# PGTNX07_gate_out.net
KiCad netlist of a schematic drawn in EAGLE
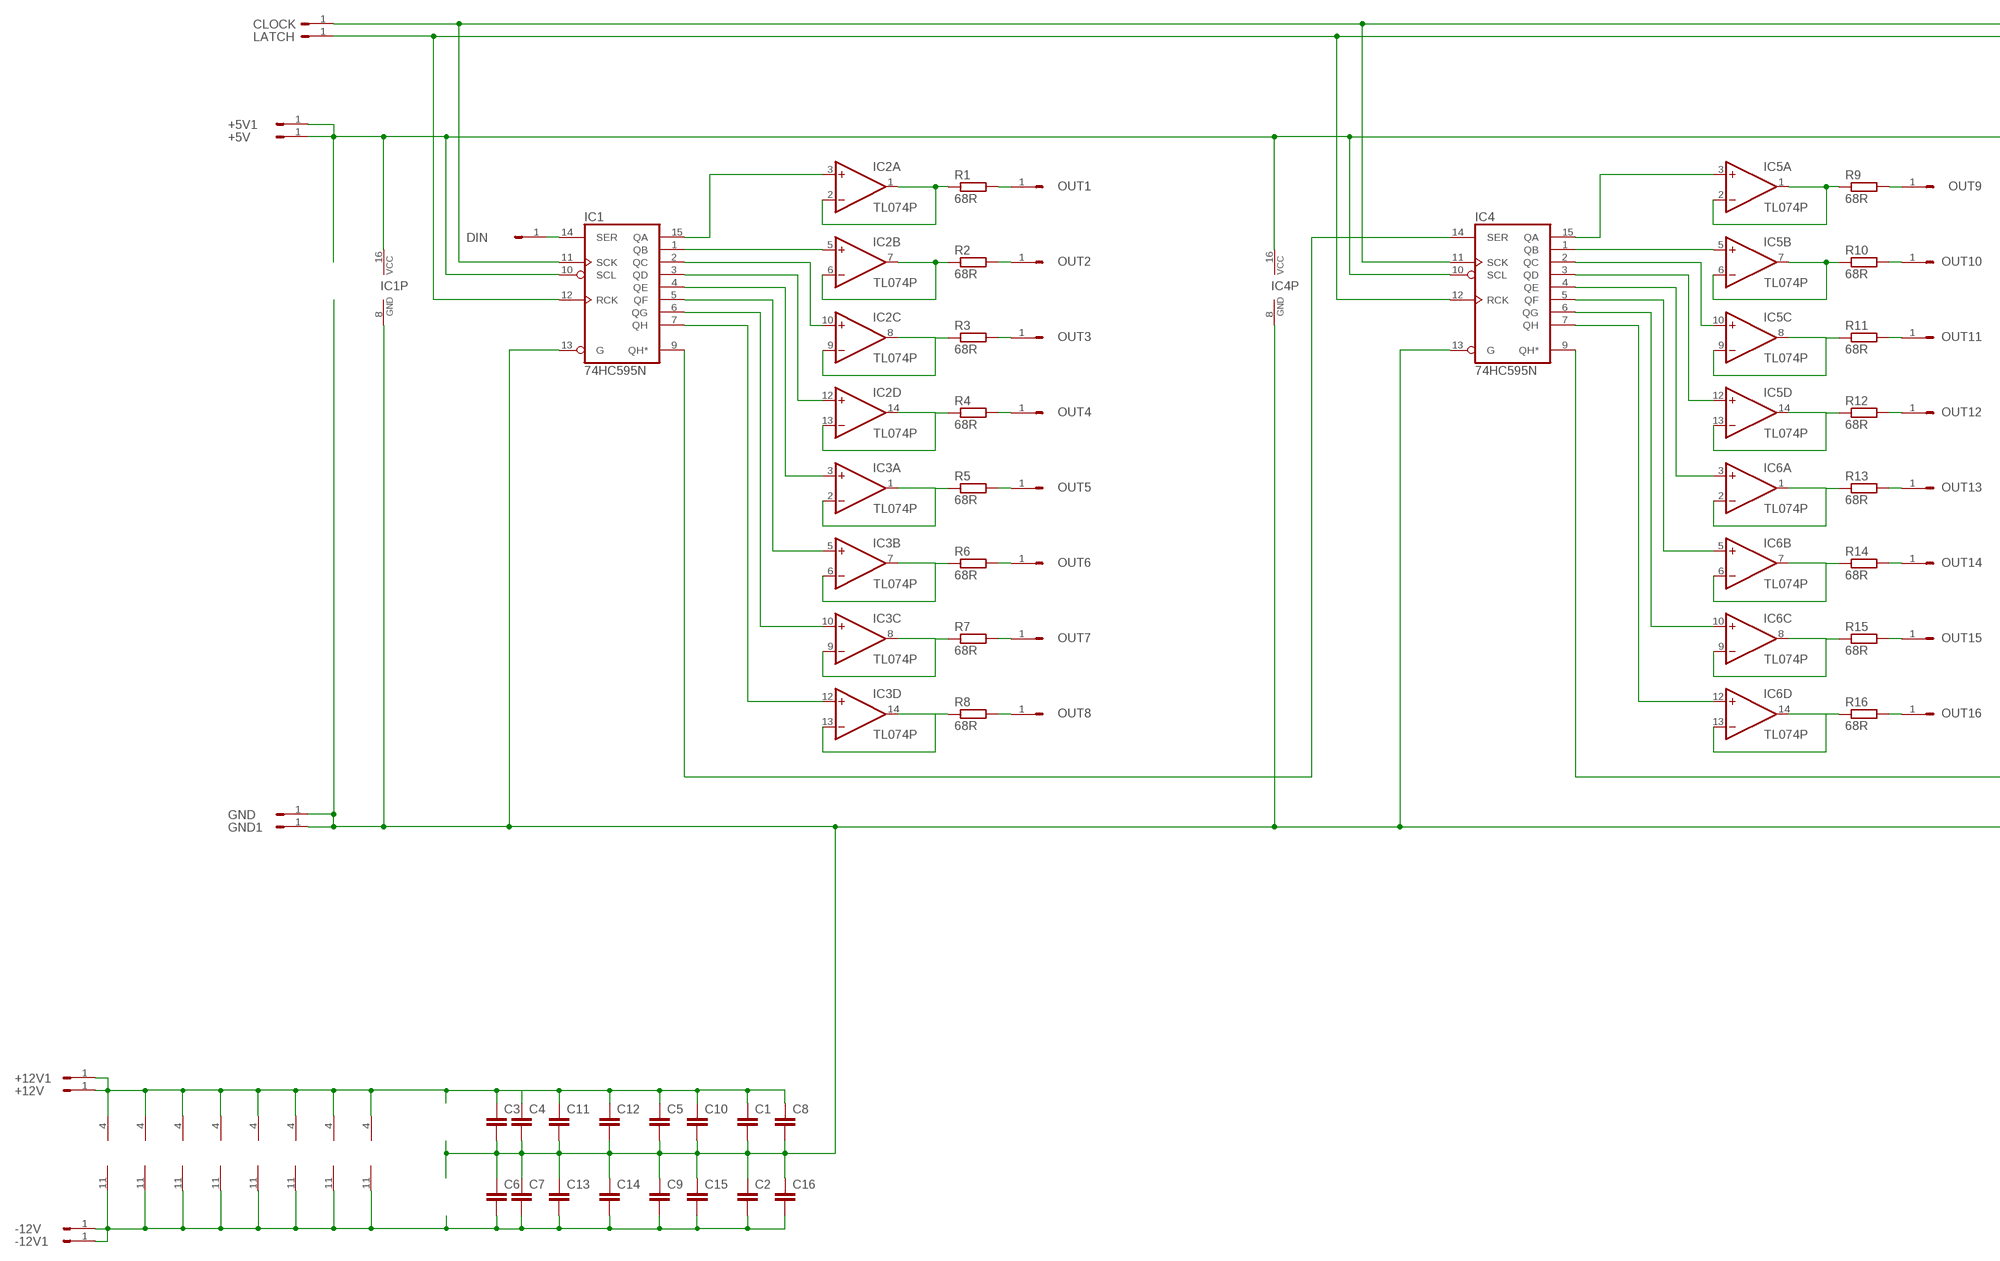
[diagram p0: schematic, sheet 1, part 1 of 2]
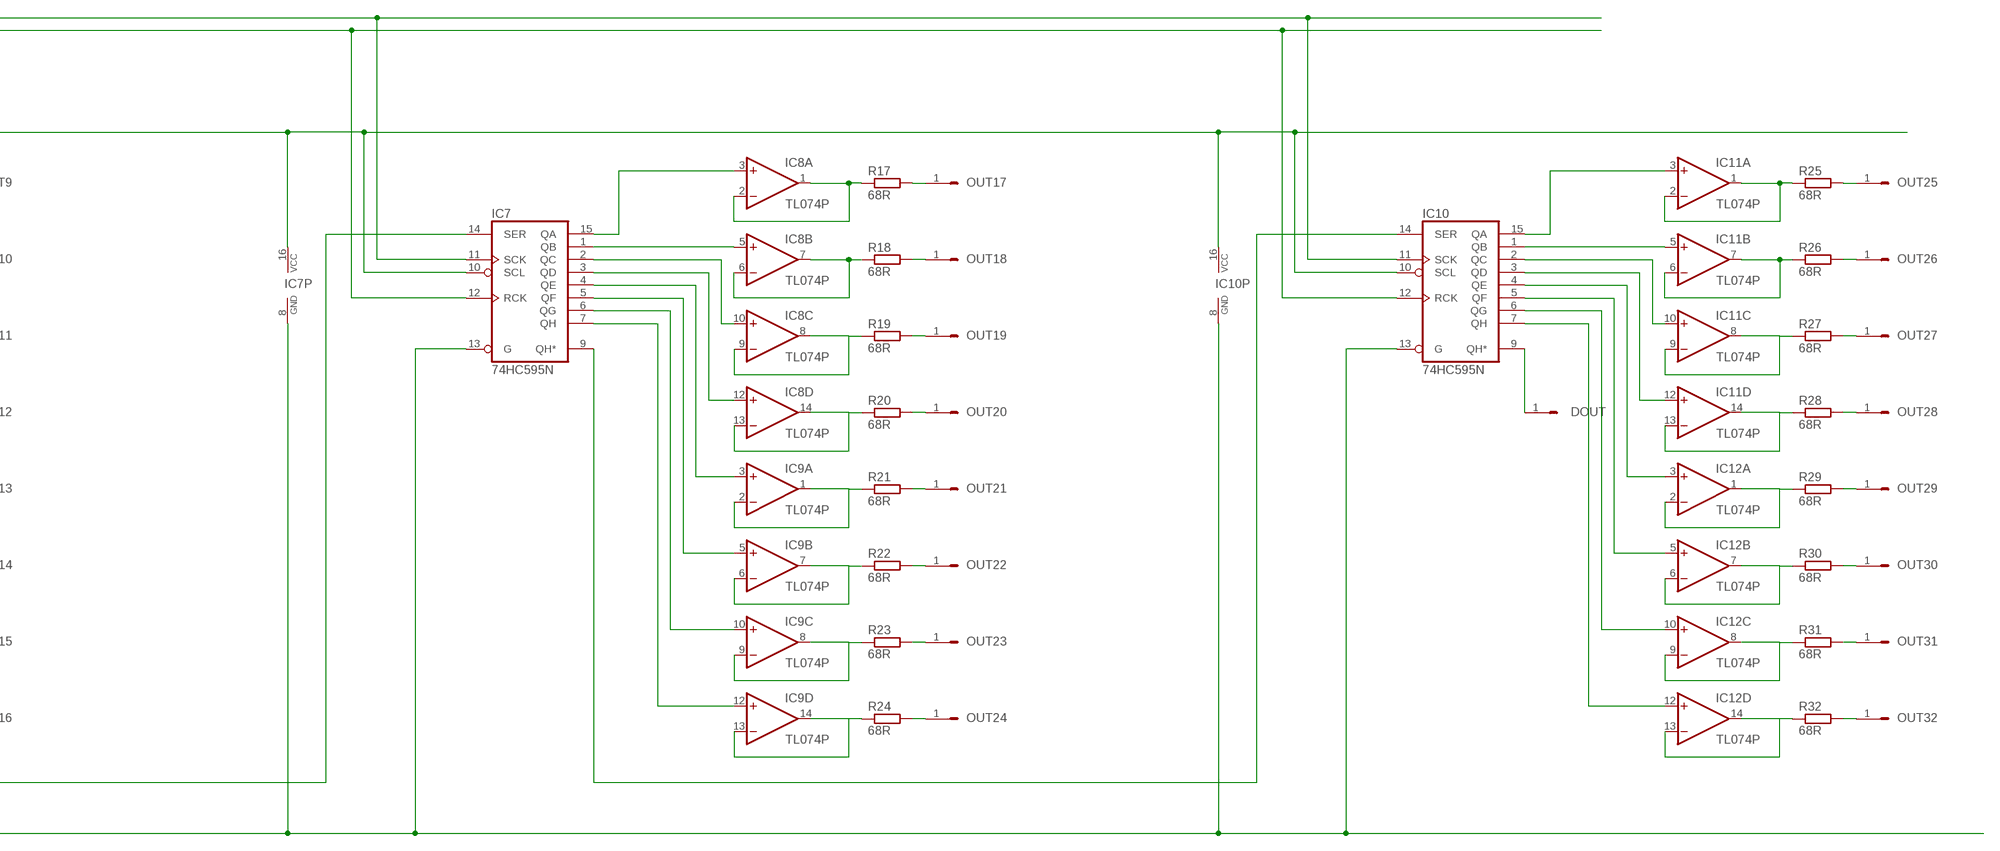
[diagram p1: schematic, sheet 1, part 2 of 2]

(export (version "E")
  (design (tool "Eeschema 10.0.6"))
  (components
    (comp (ref "+5V")
      (value "HEADER/MALE/01")
      (footprint "eagle-import:HEADER_MALE_01")
      (libsource (lib "eagle-import") (part "HEADER/MALE/01"))
    )
    (comp (ref "+5V1")
      (value "HEADER/MALE/01")
      (footprint "eagle-import:HEADER_MALE_01")
      (libsource (lib "eagle-import") (part "HEADER/MALE/01"))
    )
    (comp (ref "+12V")
      (value "HEADER/MALE/01")
      (footprint "eagle-import:HEADER_MALE_01")
      (libsource (lib "eagle-import") (part "HEADER/MALE/01"))
    )
    (comp (ref "+12V1")
      (value "HEADER/MALE/01")
      (footprint "eagle-import:HEADER_MALE_01")
      (libsource (lib "eagle-import") (part "HEADER/MALE/01"))
    )
    (comp (ref "-12V")
      (value "HEADER/MALE/01")
      (footprint "eagle-import:HEADER_MALE_01")
      (libsource (lib "eagle-import") (part "HEADER/MALE/01"))
    )
    (comp (ref "-12V1")
      (value "HEADER/MALE/01")
      (footprint "eagle-import:HEADER_MALE_01")
      (libsource (lib "eagle-import") (part "HEADER/MALE/01"))
    )
    (comp (ref "C1")
      (value "CAPACITORCERAMICDISC/5")
      (footprint "eagle-import:CERAMICDISC_5")
      (libsource (lib "eagle-import") (part "CAPACITORCERAMICDISC/5"))
    )
    (comp (ref "C2")
      (value "CAPACITORCERAMICDISC/5")
      (footprint "eagle-import:CERAMICDISC_5")
      (libsource (lib "eagle-import") (part "CAPACITORCERAMICDISC/5"))
    )
    (comp (ref "C3")
      (value "CAPACITORCERAMICDISC/5")
      (footprint "eagle-import:CERAMICDISC_5")
      (libsource (lib "eagle-import") (part "CAPACITORCERAMICDISC/5"))
    )
    (comp (ref "C4")
      (value "CAPACITORCERAMICDISC/5")
      (footprint "eagle-import:CERAMICDISC_5")
      (libsource (lib "eagle-import") (part "CAPACITORCERAMICDISC/5"))
    )
    (comp (ref "C5")
      (value "CAPACITORCERAMICDISC/5")
      (footprint "eagle-import:CERAMICDISC_5")
      (libsource (lib "eagle-import") (part "CAPACITORCERAMICDISC/5"))
    )
    (comp (ref "C6")
      (value "CAPACITORCERAMICDISC/5")
      (footprint "eagle-import:CERAMICDISC_5")
      (libsource (lib "eagle-import") (part "CAPACITORCERAMICDISC/5"))
    )
    (comp (ref "C7")
      (value "CAPACITORCERAMICDISC/5")
      (footprint "eagle-import:CERAMICDISC_5")
      (libsource (lib "eagle-import") (part "CAPACITORCERAMICDISC/5"))
    )
    (comp (ref "C8")
      (value "CAPACITORCERAMICDISC/5")
      (footprint "eagle-import:CERAMICDISC_5")
      (libsource (lib "eagle-import") (part "CAPACITORCERAMICDISC/5"))
    )
    (comp (ref "C9")
      (value "CAPACITORCERAMICDISC/5")
      (footprint "eagle-import:CERAMICDISC_5")
      (libsource (lib "eagle-import") (part "CAPACITORCERAMICDISC/5"))
    )
    (comp (ref "C10")
      (value "CAPACITORCERAMICDISC/5")
      (footprint "eagle-import:CERAMICDISC_5")
      (libsource (lib "eagle-import") (part "CAPACITORCERAMICDISC/5"))
    )
    (comp (ref "C11")
      (value "CAPACITORCERAMICDISC/5")
      (footprint "eagle-import:CERAMICDISC_5")
      (libsource (lib "eagle-import") (part "CAPACITORCERAMICDISC/5"))
    )
    (comp (ref "C12")
      (value "CAPACITORCERAMICDISC/5")
      (footprint "eagle-import:CERAMICDISC_5")
      (libsource (lib "eagle-import") (part "CAPACITORCERAMICDISC/5"))
    )
    (comp (ref "C13")
      (value "CAPACITORCERAMICDISC/5")
      (footprint "eagle-import:CERAMICDISC_5")
      (libsource (lib "eagle-import") (part "CAPACITORCERAMICDISC/5"))
    )
    (comp (ref "C14")
      (value "CAPACITORCERAMICDISC/5")
      (footprint "eagle-import:CERAMICDISC_5")
      (libsource (lib "eagle-import") (part "CAPACITORCERAMICDISC/5"))
    )
    (comp (ref "C15")
      (value "CAPACITORCERAMICDISC/5")
      (footprint "eagle-import:CERAMICDISC_5")
      (libsource (lib "eagle-import") (part "CAPACITORCERAMICDISC/5"))
    )
    (comp (ref "C16")
      (value "CAPACITORCERAMICDISC/5")
      (footprint "eagle-import:CERAMICDISC_5")
      (libsource (lib "eagle-import") (part "CAPACITORCERAMICDISC/5"))
    )
    (comp (ref "CLOCK")
      (value "HEADER/MALE/01")
      (footprint "eagle-import:HEADER_MALE_01")
      (libsource (lib "eagle-import") (part "HEADER/MALE/01"))
    )
    (comp (ref "DIN")
      (value "HEADER/MALE/01")
      (footprint "eagle-import:HEADER_MALE_01")
      (libsource (lib "eagle-import") (part "HEADER/MALE/01"))
    )
    (comp (ref "DOUT")
      (value "HEADER/MALE/01")
      (footprint "eagle-import:HEADER_MALE_01")
      (libsource (lib "eagle-import") (part "HEADER/MALE/01"))
    )
    (comp (ref "GND")
      (value "HEADER/MALE/01")
      (footprint "eagle-import:HEADER_MALE_01")
      (libsource (lib "eagle-import") (part "HEADER/MALE/01"))
    )
    (comp (ref "GND1")
      (value "HEADER/MALE/01")
      (footprint "eagle-import:HEADER_MALE_01")
      (libsource (lib "eagle-import") (part "HEADER/MALE/01"))
    )
    (comp (ref "IC1")
      (value "74HC595N")
      (footprint "eagle-import:DIL16")
      (libsource (lib "eagle-import") (part "74595NHC"))
    )
    (comp (ref "IC2")
      (value "TL074P")
      (footprint "eagle-import:DIL14")
      (libsource (lib "eagle-import") (part "TL074P"))
    )
    (comp (ref "IC3")
      (value "TL074P")
      (footprint "eagle-import:DIL14")
      (libsource (lib "eagle-import") (part "TL074P"))
    )
    (comp (ref "IC4")
      (value "74HC595N")
      (footprint "eagle-import:DIL16")
      (libsource (lib "eagle-import") (part "74595NHC"))
    )
    (comp (ref "IC5")
      (value "TL074P")
      (footprint "eagle-import:DIL14")
      (libsource (lib "eagle-import") (part "TL074P"))
    )
    (comp (ref "IC6")
      (value "TL074P")
      (footprint "eagle-import:DIL14")
      (libsource (lib "eagle-import") (part "TL074P"))
    )
    (comp (ref "IC7")
      (value "74HC595N")
      (footprint "eagle-import:DIL16")
      (libsource (lib "eagle-import") (part "74595NHC"))
    )
    (comp (ref "IC8")
      (value "TL074P")
      (footprint "eagle-import:DIL14")
      (libsource (lib "eagle-import") (part "TL074P"))
    )
    (comp (ref "IC9")
      (value "TL074P")
      (footprint "eagle-import:DIL14")
      (libsource (lib "eagle-import") (part "TL074P"))
    )
    (comp (ref "IC10")
      (value "74HC595N")
      (footprint "eagle-import:DIL16")
      (libsource (lib "eagle-import") (part "74595NHC"))
    )
    (comp (ref "IC11")
      (value "TL074P")
      (footprint "eagle-import:DIL14")
      (libsource (lib "eagle-import") (part "TL074P"))
    )
    (comp (ref "IC12")
      (value "TL074P")
      (footprint "eagle-import:DIL14")
      (libsource (lib "eagle-import") (part "TL074P"))
    )
    (comp (ref "LATCH")
      (value "HEADER/MALE/01")
      (footprint "eagle-import:HEADER_MALE_01")
      (libsource (lib "eagle-import") (part "HEADER/MALE/01"))
    )
    (comp (ref "OUT1")
      (value "HEADER/MALE/01")
      (footprint "eagle-import:HEADER_MALE_01")
      (libsource (lib "eagle-import") (part "HEADER/MALE/01"))
    )
    (comp (ref "OUT2")
      (value "HEADER/MALE/01")
      (footprint "eagle-import:HEADER_MALE_01")
      (libsource (lib "eagle-import") (part "HEADER/MALE/01"))
    )
    (comp (ref "OUT3")
      (value "HEADER/MALE/01")
      (footprint "eagle-import:HEADER_MALE_01")
      (libsource (lib "eagle-import") (part "HEADER/MALE/01"))
    )
    (comp (ref "OUT4")
      (value "HEADER/MALE/01")
      (footprint "eagle-import:HEADER_MALE_01")
      (libsource (lib "eagle-import") (part "HEADER/MALE/01"))
    )
    (comp (ref "OUT5")
      (value "HEADER/MALE/01")
      (footprint "eagle-import:HEADER_MALE_01")
      (libsource (lib "eagle-import") (part "HEADER/MALE/01"))
    )
    (comp (ref "OUT6")
      (value "HEADER/MALE/01")
      (footprint "eagle-import:HEADER_MALE_01")
      (libsource (lib "eagle-import") (part "HEADER/MALE/01"))
    )
    (comp (ref "OUT7")
      (value "HEADER/MALE/01")
      (footprint "eagle-import:HEADER_MALE_01")
      (libsource (lib "eagle-import") (part "HEADER/MALE/01"))
    )
    (comp (ref "OUT8")
      (value "HEADER/MALE/01")
      (footprint "eagle-import:HEADER_MALE_01")
      (libsource (lib "eagle-import") (part "HEADER/MALE/01"))
    )
    (comp (ref "OUT9")
      (value "HEADER/MALE/01")
      (footprint "eagle-import:HEADER_MALE_01")
      (libsource (lib "eagle-import") (part "HEADER/MALE/01"))
    )
    (comp (ref "OUT10")
      (value "HEADER/MALE/01")
      (footprint "eagle-import:HEADER_MALE_01")
      (libsource (lib "eagle-import") (part "HEADER/MALE/01"))
    )
    (comp (ref "OUT11")
      (value "HEADER/MALE/01")
      (footprint "eagle-import:HEADER_MALE_01")
      (libsource (lib "eagle-import") (part "HEADER/MALE/01"))
    )
    (comp (ref "OUT12")
      (value "HEADER/MALE/01")
      (footprint "eagle-import:HEADER_MALE_01")
      (libsource (lib "eagle-import") (part "HEADER/MALE/01"))
    )
    (comp (ref "OUT13")
      (value "HEADER/MALE/01")
      (footprint "eagle-import:HEADER_MALE_01")
      (libsource (lib "eagle-import") (part "HEADER/MALE/01"))
    )
    (comp (ref "OUT14")
      (value "HEADER/MALE/01")
      (footprint "eagle-import:HEADER_MALE_01")
      (libsource (lib "eagle-import") (part "HEADER/MALE/01"))
    )
    (comp (ref "OUT15")
      (value "HEADER/MALE/01")
      (footprint "eagle-import:HEADER_MALE_01")
      (libsource (lib "eagle-import") (part "HEADER/MALE/01"))
    )
    (comp (ref "OUT16")
      (value "HEADER/MALE/01")
      (footprint "eagle-import:HEADER_MALE_01")
      (libsource (lib "eagle-import") (part "HEADER/MALE/01"))
    )
    (comp (ref "OUT17")
      (value "HEADER/MALE/01")
      (footprint "eagle-import:HEADER_MALE_01")
      (libsource (lib "eagle-import") (part "HEADER/MALE/01"))
    )
    (comp (ref "OUT18")
      (value "HEADER/MALE/01")
      (footprint "eagle-import:HEADER_MALE_01")
      (libsource (lib "eagle-import") (part "HEADER/MALE/01"))
    )
    (comp (ref "OUT19")
      (value "HEADER/MALE/01")
      (footprint "eagle-import:HEADER_MALE_01")
      (libsource (lib "eagle-import") (part "HEADER/MALE/01"))
    )
    (comp (ref "OUT20")
      (value "HEADER/MALE/01")
      (footprint "eagle-import:HEADER_MALE_01")
      (libsource (lib "eagle-import") (part "HEADER/MALE/01"))
    )
    (comp (ref "OUT21")
      (value "HEADER/MALE/01")
      (footprint "eagle-import:HEADER_MALE_01")
      (libsource (lib "eagle-import") (part "HEADER/MALE/01"))
    )
    (comp (ref "OUT22")
      (value "HEADER/MALE/01")
      (footprint "eagle-import:HEADER_MALE_01")
      (libsource (lib "eagle-import") (part "HEADER/MALE/01"))
    )
    (comp (ref "OUT23")
      (value "HEADER/MALE/01")
      (footprint "eagle-import:HEADER_MALE_01")
      (libsource (lib "eagle-import") (part "HEADER/MALE/01"))
    )
    (comp (ref "OUT24")
      (value "HEADER/MALE/01")
      (footprint "eagle-import:HEADER_MALE_01")
      (libsource (lib "eagle-import") (part "HEADER/MALE/01"))
    )
    (comp (ref "OUT25")
      (value "HEADER/MALE/01")
      (footprint "eagle-import:HEADER_MALE_01")
      (libsource (lib "eagle-import") (part "HEADER/MALE/01"))
    )
    (comp (ref "OUT26")
      (value "HEADER/MALE/01")
      (footprint "eagle-import:HEADER_MALE_01")
      (libsource (lib "eagle-import") (part "HEADER/MALE/01"))
    )
    (comp (ref "OUT27")
      (value "HEADER/MALE/01")
      (footprint "eagle-import:HEADER_MALE_01")
      (libsource (lib "eagle-import") (part "HEADER/MALE/01"))
    )
    (comp (ref "OUT28")
      (value "HEADER/MALE/01")
      (footprint "eagle-import:HEADER_MALE_01")
      (libsource (lib "eagle-import") (part "HEADER/MALE/01"))
    )
    (comp (ref "OUT29")
      (value "HEADER/MALE/01")
      (footprint "eagle-import:HEADER_MALE_01")
      (libsource (lib "eagle-import") (part "HEADER/MALE/01"))
    )
    (comp (ref "OUT30")
      (value "HEADER/MALE/01")
      (footprint "eagle-import:HEADER_MALE_01")
      (libsource (lib "eagle-import") (part "HEADER/MALE/01"))
    )
    (comp (ref "OUT31")
      (value "HEADER/MALE/01")
      (footprint "eagle-import:HEADER_MALE_01")
      (libsource (lib "eagle-import") (part "HEADER/MALE/01"))
    )
    (comp (ref "OUT32")
      (value "HEADER/MALE/01")
      (footprint "eagle-import:HEADER_MALE_01")
      (libsource (lib "eagle-import") (part "HEADER/MALE/01"))
    )
    (comp (ref "R1")
      (value "68R")
      (footprint "eagle-import:RESISTOR_7.5")
      (libsource (lib "eagle-import") (part "RESISTORRESISTOR/UPRIGHT/7.5"))
    )
    (comp (ref "R2")
      (value "68R")
      (footprint "eagle-import:RESISTOR_7.5")
      (libsource (lib "eagle-import") (part "RESISTORRESISTOR/UPRIGHT/7.5"))
    )
    (comp (ref "R3")
      (value "68R")
      (footprint "eagle-import:RESISTOR_7.5")
      (libsource (lib "eagle-import") (part "RESISTORRESISTOR/UPRIGHT/7.5"))
    )
    (comp (ref "R4")
      (value "68R")
      (footprint "eagle-import:RESISTOR_7.5")
      (libsource (lib "eagle-import") (part "RESISTORRESISTOR/UPRIGHT/7.5"))
    )
    (comp (ref "R5")
      (value "68R")
      (footprint "eagle-import:RESISTOR_7.5")
      (libsource (lib "eagle-import") (part "RESISTORRESISTOR/UPRIGHT/7.5"))
    )
    (comp (ref "R6")
      (value "68R")
      (footprint "eagle-import:RESISTOR_7.5")
      (libsource (lib "eagle-import") (part "RESISTORRESISTOR/UPRIGHT/7.5"))
    )
    (comp (ref "R7")
      (value "68R")
      (footprint "eagle-import:RESISTOR_7.5")
      (libsource (lib "eagle-import") (part "RESISTORRESISTOR/UPRIGHT/7.5"))
    )
    (comp (ref "R8")
      (value "68R")
      (footprint "eagle-import:RESISTOR_7.5")
      (libsource (lib "eagle-import") (part "RESISTORRESISTOR/UPRIGHT/7.5"))
    )
    (comp (ref "R9")
      (value "68R")
      (footprint "eagle-import:RESISTOR_7.5")
      (libsource (lib "eagle-import") (part "RESISTORRESISTOR/UPRIGHT/7.5"))
    )
    (comp (ref "R10")
      (value "68R")
      (footprint "eagle-import:RESISTOR_7.5")
      (libsource (lib "eagle-import") (part "RESISTORRESISTOR/UPRIGHT/7.5"))
    )
    (comp (ref "R11")
      (value "68R")
      (footprint "eagle-import:RESISTOR_7.5")
      (libsource (lib "eagle-import") (part "RESISTORRESISTOR/UPRIGHT/7.5"))
    )
    (comp (ref "R12")
      (value "68R")
      (footprint "eagle-import:RESISTOR_7.5")
      (libsource (lib "eagle-import") (part "RESISTORRESISTOR/UPRIGHT/7.5"))
    )
    (comp (ref "R13")
      (value "68R")
      (footprint "eagle-import:RESISTOR_7.5")
      (libsource (lib "eagle-import") (part "RESISTORRESISTOR/UPRIGHT/7.5"))
    )
    (comp (ref "R14")
      (value "68R")
      (footprint "eagle-import:RESISTOR_7.5")
      (libsource (lib "eagle-import") (part "RESISTORRESISTOR/UPRIGHT/7.5"))
    )
    (comp (ref "R15")
      (value "68R")
      (footprint "eagle-import:RESISTOR_7.5")
      (libsource (lib "eagle-import") (part "RESISTORRESISTOR/UPRIGHT/7.5"))
    )
    (comp (ref "R16")
      (value "68R")
      (footprint "eagle-import:RESISTOR_7.5")
      (libsource (lib "eagle-import") (part "RESISTORRESISTOR/UPRIGHT/7.5"))
    )
    (comp (ref "R17")
      (value "68R")
      (footprint "eagle-import:RESISTOR_7.5")
      (libsource (lib "eagle-import") (part "RESISTORRESISTOR/UPRIGHT/7.5"))
    )
    (comp (ref "R18")
      (value "68R")
      (footprint "eagle-import:RESISTOR_7.5")
      (libsource (lib "eagle-import") (part "RESISTORRESISTOR/UPRIGHT/7.5"))
    )
    (comp (ref "R19")
      (value "68R")
      (footprint "eagle-import:RESISTOR_7.5")
      (libsource (lib "eagle-import") (part "RESISTORRESISTOR/UPRIGHT/7.5"))
    )
    (comp (ref "R20")
      (value "68R")
      (footprint "eagle-import:RESISTOR_7.5")
      (libsource (lib "eagle-import") (part "RESISTORRESISTOR/UPRIGHT/7.5"))
    )
    (comp (ref "R21")
      (value "68R")
      (footprint "eagle-import:RESISTOR_7.5")
      (libsource (lib "eagle-import") (part "RESISTORRESISTOR/UPRIGHT/7.5"))
    )
    (comp (ref "R22")
      (value "68R")
      (footprint "eagle-import:RESISTOR_7.5")
      (libsource (lib "eagle-import") (part "RESISTORRESISTOR/UPRIGHT/7.5"))
    )
    (comp (ref "R23")
      (value "68R")
      (footprint "eagle-import:RESISTOR_7.5")
      (libsource (lib "eagle-import") (part "RESISTORRESISTOR/UPRIGHT/7.5"))
    )
    (comp (ref "R24")
      (value "68R")
      (footprint "eagle-import:RESISTOR_7.5")
      (libsource (lib "eagle-import") (part "RESISTORRESISTOR/UPRIGHT/7.5"))
    )
    (comp (ref "R25")
      (value "68R")
      (footprint "eagle-import:RESISTOR_7.5")
      (libsource (lib "eagle-import") (part "RESISTORRESISTOR/UPRIGHT/7.5"))
    )
    (comp (ref "R26")
      (value "68R")
      (footprint "eagle-import:RESISTOR_7.5")
      (libsource (lib "eagle-import") (part "RESISTORRESISTOR/UPRIGHT/7.5"))
    )
    (comp (ref "R27")
      (value "68R")
      (footprint "eagle-import:RESISTOR_7.5")
      (libsource (lib "eagle-import") (part "RESISTORRESISTOR/UPRIGHT/7.5"))
    )
    (comp (ref "R28")
      (value "68R")
      (footprint "eagle-import:RESISTOR_7.5")
      (libsource (lib "eagle-import") (part "RESISTORRESISTOR/UPRIGHT/7.5"))
    )
    (comp (ref "R29")
      (value "68R")
      (footprint "eagle-import:RESISTOR_7.5")
      (libsource (lib "eagle-import") (part "RESISTORRESISTOR/UPRIGHT/7.5"))
    )
    (comp (ref "R30")
      (value "68R")
      (footprint "eagle-import:RESISTOR_7.5")
      (libsource (lib "eagle-import") (part "RESISTORRESISTOR/UPRIGHT/7.5"))
    )
    (comp (ref "R31")
      (value "68R")
      (footprint "eagle-import:RESISTOR_7.5")
      (libsource (lib "eagle-import") (part "RESISTORRESISTOR/UPRIGHT/7.5"))
    )
    (comp (ref "R32")
      (value "68R")
      (footprint "eagle-import:RESISTOR_7.5")
      (libsource (lib "eagle-import") (part "RESISTORRESISTOR/UPRIGHT/7.5"))
    )
  )
  (nets
    (net (code "1") (name "Net-(+5V-3)") (class "Default")
      (node (ref "+5V") (pin "1") (pinfunction "3_1") (pintype "passive"))
      (node (ref "+5V1") (pin "1") (pinfunction "3_1") (pintype "passive"))
      (node (ref "IC1") (pin "10") (pinfunction "SCL_10") (pintype "input"))
      (node (ref "IC1") (pin "16") (pinfunction "VCC_16") (pintype "power_in"))
      (node (ref "IC10") (pin "10") (pinfunction "SCL_10") (pintype "input"))
      (node (ref "IC10") (pin "16") (pinfunction "VCC_16") (pintype "power_in"))
      (node (ref "IC4") (pin "10") (pinfunction "SCL_10") (pintype "input"))
      (node (ref "IC4") (pin "16") (pinfunction "VCC_16") (pintype "power_in"))
      (node (ref "IC7") (pin "10") (pinfunction "SCL_10") (pintype "input"))
      (node (ref "IC7") (pin "16") (pinfunction "VCC_16") (pintype "power_in"))
    )
    (net (code "2") (name "Net-(+12V-3)") (class "Default")
      (node (ref "+12V") (pin "1") (pinfunction "3_1") (pintype "passive"))
      (node (ref "+12V1") (pin "1") (pinfunction "3_1") (pintype "passive"))
      (node (ref "C1") (pin "1") (pinfunction "1_1") (pintype "passive"))
      (node (ref "C10") (pin "1") (pinfunction "1_1") (pintype "passive"))
      (node (ref "C11") (pin "1") (pinfunction "1_1") (pintype "passive"))
      (node (ref "C12") (pin "1") (pinfunction "1_1") (pintype "passive"))
      (node (ref "C3") (pin "1") (pinfunction "1_1") (pintype "passive"))
      (node (ref "C4") (pin "1") (pinfunction "1_1") (pintype "passive"))
      (node (ref "C5") (pin "1") (pinfunction "1_1") (pintype "passive"))
      (node (ref "C8") (pin "1") (pinfunction "1_1") (pintype "passive"))
      (node (ref "IC11") (pin "4") (pinfunction "V+_4") (pintype "power_in"))
      (node (ref "IC12") (pin "4") (pinfunction "V+_4") (pintype "power_in"))
      (node (ref "IC2") (pin "4") (pinfunction "V+_4") (pintype "power_in"))
      (node (ref "IC3") (pin "4") (pinfunction "V+_4") (pintype "power_in"))
      (node (ref "IC5") (pin "4") (pinfunction "V+_4") (pintype "power_in"))
      (node (ref "IC6") (pin "4") (pinfunction "V+_4") (pintype "power_in"))
      (node (ref "IC8") (pin "4") (pinfunction "V+_4") (pintype "power_in"))
      (node (ref "IC9") (pin "4") (pinfunction "V+_4") (pintype "power_in"))
    )
    (net (code "3") (name "Net-(-12V-3)") (class "Default")
      (node (ref "-12V") (pin "1") (pinfunction "3_1") (pintype "passive"))
      (node (ref "-12V1") (pin "1") (pinfunction "3_1") (pintype "passive"))
      (node (ref "C13") (pin "2") (pinfunction "2_2") (pintype "passive"))
      (node (ref "C14") (pin "2") (pinfunction "2_2") (pintype "passive"))
      (node (ref "C15") (pin "2") (pinfunction "2_2") (pintype "passive"))
      (node (ref "C16") (pin "2") (pinfunction "2_2") (pintype "passive"))
      (node (ref "C2") (pin "2") (pinfunction "2_2") (pintype "passive"))
      (node (ref "C6") (pin "2") (pinfunction "2_2") (pintype "passive"))
      (node (ref "C7") (pin "2") (pinfunction "2_2") (pintype "passive"))
      (node (ref "C9") (pin "2") (pinfunction "2_2") (pintype "passive"))
      (node (ref "IC11") (pin "11") (pinfunction "V-_11") (pintype "power_in"))
      (node (ref "IC12") (pin "11") (pinfunction "V-_11") (pintype "power_in"))
      (node (ref "IC2") (pin "11") (pinfunction "V-_11") (pintype "power_in"))
      (node (ref "IC3") (pin "11") (pinfunction "V-_11") (pintype "power_in"))
      (node (ref "IC5") (pin "11") (pinfunction "V-_11") (pintype "power_in"))
      (node (ref "IC6") (pin "11") (pinfunction "V-_11") (pintype "power_in"))
      (node (ref "IC8") (pin "11") (pinfunction "V-_11") (pintype "power_in"))
      (node (ref "IC9") (pin "11") (pinfunction "V-_11") (pintype "power_in"))
    )
    (net (code "4") (name "Net-(CLOCK-3)") (class "Default")
      (node (ref "CLOCK") (pin "1") (pinfunction "3_1") (pintype "passive"))
      (node (ref "IC1") (pin "11") (pinfunction "SCK_11") (pintype "input"))
      (node (ref "IC10") (pin "11") (pinfunction "SCK_11") (pintype "input"))
      (node (ref "IC4") (pin "11") (pinfunction "SCK_11") (pintype "input"))
      (node (ref "IC7") (pin "11") (pinfunction "SCK_11") (pintype "input"))
    )
    (net (code "5") (name "Net-(DIN-3)") (class "Default")
      (node (ref "DIN") (pin "1") (pinfunction "3_1") (pintype "passive"))
      (node (ref "IC1") (pin "14") (pinfunction "SER_14") (pintype "input"))
    )
    (net (code "6") (name "Net-(DOUT-3)") (class "Default")
      (node (ref "DOUT") (pin "1") (pinfunction "3_1") (pintype "passive"))
      (node (ref "IC10") (pin "9") (pinfunction "QH*_9") (pintype "tri_state"))
    )
    (net (code "7") (name "Net-(GND-3)") (class "Default")
      (node (ref "C1") (pin "2") (pinfunction "2_2") (pintype "passive"))
      (node (ref "C10") (pin "2") (pinfunction "2_2") (pintype "passive"))
      (node (ref "C11") (pin "2") (pinfunction "2_2") (pintype "passive"))
      (node (ref "C12") (pin "2") (pinfunction "2_2") (pintype "passive"))
      (node (ref "C13") (pin "1") (pinfunction "1_1") (pintype "passive"))
      (node (ref "C14") (pin "1") (pinfunction "1_1") (pintype "passive"))
      (node (ref "C15") (pin "1") (pinfunction "1_1") (pintype "passive"))
      (node (ref "C16") (pin "1") (pinfunction "1_1") (pintype "passive"))
      (node (ref "C2") (pin "1") (pinfunction "1_1") (pintype "passive"))
      (node (ref "C3") (pin "2") (pinfunction "2_2") (pintype "passive"))
      (node (ref "C4") (pin "2") (pinfunction "2_2") (pintype "passive"))
      (node (ref "C5") (pin "2") (pinfunction "2_2") (pintype "passive"))
      (node (ref "C6") (pin "1") (pinfunction "1_1") (pintype "passive"))
      (node (ref "C7") (pin "1") (pinfunction "1_1") (pintype "passive"))
      (node (ref "C8") (pin "2") (pinfunction "2_2") (pintype "passive"))
      (node (ref "C9") (pin "1") (pinfunction "1_1") (pintype "passive"))
      (node (ref "GND") (pin "1") (pinfunction "3_1") (pintype "passive"))
      (node (ref "GND1") (pin "1") (pinfunction "3_1") (pintype "passive"))
      (node (ref "IC1") (pin "13") (pinfunction "G_13") (pintype "input"))
      (node (ref "IC1") (pin "8") (pinfunction "GND_8") (pintype "power_in"))
      (node (ref "IC10") (pin "13") (pinfunction "G_13") (pintype "input"))
      (node (ref "IC10") (pin "8") (pinfunction "GND_8") (pintype "power_in"))
      (node (ref "IC4") (pin "13") (pinfunction "G_13") (pintype "input"))
      (node (ref "IC4") (pin "8") (pinfunction "GND_8") (pintype "power_in"))
      (node (ref "IC7") (pin "13") (pinfunction "G_13") (pintype "input"))
      (node (ref "IC7") (pin "8") (pinfunction "GND_8") (pintype "power_in"))
    )
    (net (code "8") (name "Net-(IC1A-QA)") (class "Default")
      (node (ref "IC1") (pin "15") (pinfunction "QA_15") (pintype "tri_state"))
      (node (ref "IC2") (pin "3") (pinfunction "+IN_3") (pintype "input"))
    )
    (net (code "9") (name "Net-(IC1A-QB)") (class "Default")
      (node (ref "IC1") (pin "1") (pinfunction "QB_1") (pintype "tri_state"))
      (node (ref "IC2") (pin "5") (pinfunction "+IN_5") (pintype "input"))
    )
    (net (code "10") (name "Net-(IC1A-QC)") (class "Default")
      (node (ref "IC1") (pin "2") (pinfunction "QC_2") (pintype "tri_state"))
      (node (ref "IC2") (pin "10") (pinfunction "+IN_10") (pintype "input"))
    )
    (net (code "11") (name "Net-(IC1A-QD)") (class "Default")
      (node (ref "IC1") (pin "3") (pinfunction "QD_3") (pintype "tri_state"))
      (node (ref "IC2") (pin "12") (pinfunction "+IN_12") (pintype "input"))
    )
    (net (code "12") (name "Net-(IC1A-QE)") (class "Default")
      (node (ref "IC1") (pin "4") (pinfunction "QE_4") (pintype "tri_state"))
      (node (ref "IC3") (pin "3") (pinfunction "+IN_3") (pintype "input"))
    )
    (net (code "13") (name "Net-(IC1A-QF)") (class "Default")
      (node (ref "IC1") (pin "5") (pinfunction "QF_5") (pintype "tri_state"))
      (node (ref "IC3") (pin "5") (pinfunction "+IN_5") (pintype "input"))
    )
    (net (code "14") (name "Net-(IC1A-QG)") (class "Default")
      (node (ref "IC1") (pin "6") (pinfunction "QG_6") (pintype "tri_state"))
      (node (ref "IC3") (pin "10") (pinfunction "+IN_10") (pintype "input"))
    )
    (net (code "15") (name "Net-(IC1A-QH)") (class "Default")
      (node (ref "IC1") (pin "7") (pinfunction "QH_7") (pintype "tri_state"))
      (node (ref "IC3") (pin "12") (pinfunction "+IN_12") (pintype "input"))
    )
    (net (code "16") (name "Net-(IC1A-QH*)") (class "Default")
      (node (ref "IC1") (pin "9") (pinfunction "QH*_9") (pintype "tri_state"))
      (node (ref "IC4") (pin "14") (pinfunction "SER_14") (pintype "input"))
    )
    (net (code "17") (name "Net-(IC2A--IN)") (class "Default")
      (node (ref "IC2") (pin "1") (pinfunction "OUT_1") (pintype "output"))
      (node (ref "IC2") (pin "2") (pinfunction "-IN_2") (pintype "input"))
      (node (ref "R1") (pin "1") (pinfunction "1_1") (pintype "passive"))
    )
    (net (code "18") (name "Net-(IC2B--IN)") (class "Default")
      (node (ref "IC2") (pin "6") (pinfunction "-IN_6") (pintype "input"))
      (node (ref "IC2") (pin "7") (pinfunction "OUT_7") (pintype "output"))
      (node (ref "R2") (pin "1") (pinfunction "1_1") (pintype "passive"))
    )
    (net (code "19") (name "Net-(IC2C--IN)") (class "Default")
      (node (ref "IC2") (pin "8") (pinfunction "OUT_8") (pintype "output"))
      (node (ref "IC2") (pin "9") (pinfunction "-IN_9") (pintype "input"))
      (node (ref "R3") (pin "1") (pinfunction "1_1") (pintype "passive"))
    )
    (net (code "20") (name "Net-(IC2D--IN)") (class "Default")
      (node (ref "IC2") (pin "13") (pinfunction "-IN_13") (pintype "input"))
      (node (ref "IC2") (pin "14") (pinfunction "OUT_14") (pintype "output"))
      (node (ref "R4") (pin "1") (pinfunction "1_1") (pintype "passive"))
    )
    (net (code "21") (name "Net-(IC3A--IN)") (class "Default")
      (node (ref "IC3") (pin "1") (pinfunction "OUT_1") (pintype "output"))
      (node (ref "IC3") (pin "2") (pinfunction "-IN_2") (pintype "input"))
      (node (ref "R5") (pin "1") (pinfunction "1_1") (pintype "passive"))
    )
    (net (code "22") (name "Net-(IC3B--IN)") (class "Default")
      (node (ref "IC3") (pin "6") (pinfunction "-IN_6") (pintype "input"))
      (node (ref "IC3") (pin "7") (pinfunction "OUT_7") (pintype "output"))
      (node (ref "R6") (pin "1") (pinfunction "1_1") (pintype "passive"))
    )
    (net (code "23") (name "Net-(IC3C--IN)") (class "Default")
      (node (ref "IC3") (pin "8") (pinfunction "OUT_8") (pintype "output"))
      (node (ref "IC3") (pin "9") (pinfunction "-IN_9") (pintype "input"))
      (node (ref "R7") (pin "1") (pinfunction "1_1") (pintype "passive"))
    )
    (net (code "24") (name "Net-(IC3D--IN)") (class "Default")
      (node (ref "IC3") (pin "13") (pinfunction "-IN_13") (pintype "input"))
      (node (ref "IC3") (pin "14") (pinfunction "OUT_14") (pintype "output"))
      (node (ref "R8") (pin "1") (pinfunction "1_1") (pintype "passive"))
    )
    (net (code "25") (name "Net-(IC4A-QA)") (class "Default")
      (node (ref "IC4") (pin "15") (pinfunction "QA_15") (pintype "tri_state"))
      (node (ref "IC5") (pin "3") (pinfunction "+IN_3") (pintype "input"))
    )
    (net (code "26") (name "Net-(IC4A-QB)") (class "Default")
      (node (ref "IC4") (pin "1") (pinfunction "QB_1") (pintype "tri_state"))
      (node (ref "IC5") (pin "5") (pinfunction "+IN_5") (pintype "input"))
    )
    (net (code "27") (name "Net-(IC4A-QC)") (class "Default")
      (node (ref "IC4") (pin "2") (pinfunction "QC_2") (pintype "tri_state"))
      (node (ref "IC5") (pin "10") (pinfunction "+IN_10") (pintype "input"))
    )
    (net (code "28") (name "Net-(IC4A-QD)") (class "Default")
      (node (ref "IC4") (pin "3") (pinfunction "QD_3") (pintype "tri_state"))
      (node (ref "IC5") (pin "12") (pinfunction "+IN_12") (pintype "input"))
    )
    (net (code "29") (name "Net-(IC4A-QE)") (class "Default")
      (node (ref "IC4") (pin "4") (pinfunction "QE_4") (pintype "tri_state"))
      (node (ref "IC6") (pin "3") (pinfunction "+IN_3") (pintype "input"))
    )
    (net (code "30") (name "Net-(IC4A-QF)") (class "Default")
      (node (ref "IC4") (pin "5") (pinfunction "QF_5") (pintype "tri_state"))
      (node (ref "IC6") (pin "5") (pinfunction "+IN_5") (pintype "input"))
    )
    (net (code "31") (name "Net-(IC4A-QG)") (class "Default")
      (node (ref "IC4") (pin "6") (pinfunction "QG_6") (pintype "tri_state"))
      (node (ref "IC6") (pin "10") (pinfunction "+IN_10") (pintype "input"))
    )
    (net (code "32") (name "Net-(IC4A-QH)") (class "Default")
      (node (ref "IC4") (pin "7") (pinfunction "QH_7") (pintype "tri_state"))
      (node (ref "IC6") (pin "12") (pinfunction "+IN_12") (pintype "input"))
    )
    (net (code "33") (name "Net-(IC4A-QH*)") (class "Default")
      (node (ref "IC4") (pin "9") (pinfunction "QH*_9") (pintype "tri_state"))
      (node (ref "IC7") (pin "14") (pinfunction "SER_14") (pintype "input"))
    )
    (net (code "34") (name "Net-(IC5A--IN)") (class "Default")
      (node (ref "IC5") (pin "1") (pinfunction "OUT_1") (pintype "output"))
      (node (ref "IC5") (pin "2") (pinfunction "-IN_2") (pintype "input"))
      (node (ref "R9") (pin "1") (pinfunction "1_1") (pintype "passive"))
    )
    (net (code "35") (name "Net-(IC5B--IN)") (class "Default")
      (node (ref "IC5") (pin "6") (pinfunction "-IN_6") (pintype "input"))
      (node (ref "IC5") (pin "7") (pinfunction "OUT_7") (pintype "output"))
      (node (ref "R10") (pin "1") (pinfunction "1_1") (pintype "passive"))
    )
    (net (code "36") (name "Net-(IC5C--IN)") (class "Default")
      (node (ref "IC5") (pin "8") (pinfunction "OUT_8") (pintype "output"))
      (node (ref "IC5") (pin "9") (pinfunction "-IN_9") (pintype "input"))
      (node (ref "R11") (pin "1") (pinfunction "1_1") (pintype "passive"))
    )
    (net (code "37") (name "Net-(IC5D--IN)") (class "Default")
      (node (ref "IC5") (pin "13") (pinfunction "-IN_13") (pintype "input"))
      (node (ref "IC5") (pin "14") (pinfunction "OUT_14") (pintype "output"))
      (node (ref "R12") (pin "1") (pinfunction "1_1") (pintype "passive"))
    )
    (net (code "38") (name "Net-(IC6A--IN)") (class "Default")
      (node (ref "IC6") (pin "1") (pinfunction "OUT_1") (pintype "output"))
      (node (ref "IC6") (pin "2") (pinfunction "-IN_2") (pintype "input"))
      (node (ref "R13") (pin "1") (pinfunction "1_1") (pintype "passive"))
    )
    (net (code "39") (name "Net-(IC6B--IN)") (class "Default")
      (node (ref "IC6") (pin "6") (pinfunction "-IN_6") (pintype "input"))
      (node (ref "IC6") (pin "7") (pinfunction "OUT_7") (pintype "output"))
      (node (ref "R14") (pin "1") (pinfunction "1_1") (pintype "passive"))
    )
    (net (code "40") (name "Net-(IC6C--IN)") (class "Default")
      (node (ref "IC6") (pin "8") (pinfunction "OUT_8") (pintype "output"))
      (node (ref "IC6") (pin "9") (pinfunction "-IN_9") (pintype "input"))
      (node (ref "R15") (pin "1") (pinfunction "1_1") (pintype "passive"))
    )
    (net (code "41") (name "Net-(IC6D--IN)") (class "Default")
      (node (ref "IC6") (pin "13") (pinfunction "-IN_13") (pintype "input"))
      (node (ref "IC6") (pin "14") (pinfunction "OUT_14") (pintype "output"))
      (node (ref "R16") (pin "1") (pinfunction "1_1") (pintype "passive"))
    )
    (net (code "42") (name "Net-(IC7A-QA)") (class "Default")
      (node (ref "IC7") (pin "15") (pinfunction "QA_15") (pintype "tri_state"))
      (node (ref "IC8") (pin "3") (pinfunction "+IN_3") (pintype "input"))
    )
    (net (code "43") (name "Net-(IC7A-QB)") (class "Default")
      (node (ref "IC7") (pin "1") (pinfunction "QB_1") (pintype "tri_state"))
      (node (ref "IC8") (pin "5") (pinfunction "+IN_5") (pintype "input"))
    )
    (net (code "44") (name "Net-(IC7A-QC)") (class "Default")
      (node (ref "IC7") (pin "2") (pinfunction "QC_2") (pintype "tri_state"))
      (node (ref "IC8") (pin "10") (pinfunction "+IN_10") (pintype "input"))
    )
    (net (code "45") (name "Net-(IC7A-QD)") (class "Default")
      (node (ref "IC7") (pin "3") (pinfunction "QD_3") (pintype "tri_state"))
      (node (ref "IC8") (pin "12") (pinfunction "+IN_12") (pintype "input"))
    )
    (net (code "46") (name "Net-(IC7A-QE)") (class "Default")
      (node (ref "IC7") (pin "4") (pinfunction "QE_4") (pintype "tri_state"))
      (node (ref "IC9") (pin "3") (pinfunction "+IN_3") (pintype "input"))
    )
    (net (code "47") (name "Net-(IC7A-QF)") (class "Default")
      (node (ref "IC7") (pin "5") (pinfunction "QF_5") (pintype "tri_state"))
      (node (ref "IC9") (pin "5") (pinfunction "+IN_5") (pintype "input"))
    )
    (net (code "48") (name "Net-(IC7A-QG)") (class "Default")
      (node (ref "IC7") (pin "6") (pinfunction "QG_6") (pintype "tri_state"))
      (node (ref "IC9") (pin "10") (pinfunction "+IN_10") (pintype "input"))
    )
    (net (code "49") (name "Net-(IC7A-QH)") (class "Default")
      (node (ref "IC7") (pin "7") (pinfunction "QH_7") (pintype "tri_state"))
      (node (ref "IC9") (pin "12") (pinfunction "+IN_12") (pintype "input"))
    )
    (net (code "50") (name "Net-(IC8A--IN)") (class "Default")
      (node (ref "IC8") (pin "1") (pinfunction "OUT_1") (pintype "output"))
      (node (ref "IC8") (pin "2") (pinfunction "-IN_2") (pintype "input"))
      (node (ref "R17") (pin "1") (pinfunction "1_1") (pintype "passive"))
    )
    (net (code "51") (name "Net-(IC8B--IN)") (class "Default")
      (node (ref "IC8") (pin "6") (pinfunction "-IN_6") (pintype "input"))
      (node (ref "IC8") (pin "7") (pinfunction "OUT_7") (pintype "output"))
      (node (ref "R18") (pin "1") (pinfunction "1_1") (pintype "passive"))
    )
    (net (code "52") (name "Net-(IC8C--IN)") (class "Default")
      (node (ref "IC8") (pin "8") (pinfunction "OUT_8") (pintype "output"))
      (node (ref "IC8") (pin "9") (pinfunction "-IN_9") (pintype "input"))
      (node (ref "R19") (pin "1") (pinfunction "1_1") (pintype "passive"))
    )
    (net (code "53") (name "Net-(IC8D--IN)") (class "Default")
      (node (ref "IC8") (pin "13") (pinfunction "-IN_13") (pintype "input"))
      (node (ref "IC8") (pin "14") (pinfunction "OUT_14") (pintype "output"))
      (node (ref "R20") (pin "1") (pinfunction "1_1") (pintype "passive"))
    )
    (net (code "54") (name "Net-(IC9A--IN)") (class "Default")
      (node (ref "IC9") (pin "1") (pinfunction "OUT_1") (pintype "output"))
      (node (ref "IC9") (pin "2") (pinfunction "-IN_2") (pintype "input"))
      (node (ref "R21") (pin "1") (pinfunction "1_1") (pintype "passive"))
    )
    (net (code "55") (name "Net-(IC9B--IN)") (class "Default")
      (node (ref "IC9") (pin "6") (pinfunction "-IN_6") (pintype "input"))
      (node (ref "IC9") (pin "7") (pinfunction "OUT_7") (pintype "output"))
      (node (ref "R22") (pin "1") (pinfunction "1_1") (pintype "passive"))
    )
    (net (code "56") (name "Net-(IC9C--IN)") (class "Default")
      (node (ref "IC9") (pin "8") (pinfunction "OUT_8") (pintype "output"))
      (node (ref "IC9") (pin "9") (pinfunction "-IN_9") (pintype "input"))
      (node (ref "R23") (pin "1") (pinfunction "1_1") (pintype "passive"))
    )
    (net (code "57") (name "Net-(IC9D--IN)") (class "Default")
      (node (ref "IC9") (pin "13") (pinfunction "-IN_13") (pintype "input"))
      (node (ref "IC9") (pin "14") (pinfunction "OUT_14") (pintype "output"))
      (node (ref "R24") (pin "1") (pinfunction "1_1") (pintype "passive"))
    )
    (net (code "58") (name "Net-(IC10A-QA)") (class "Default")
      (node (ref "IC10") (pin "15") (pinfunction "QA_15") (pintype "tri_state"))
      (node (ref "IC11") (pin "3") (pinfunction "+IN_3") (pintype "input"))
    )
    (net (code "59") (name "Net-(IC10A-QB)") (class "Default")
      (node (ref "IC10") (pin "1") (pinfunction "QB_1") (pintype "tri_state"))
      (node (ref "IC11") (pin "5") (pinfunction "+IN_5") (pintype "input"))
    )
    (net (code "60") (name "Net-(IC10A-QC)") (class "Default")
      (node (ref "IC10") (pin "2") (pinfunction "QC_2") (pintype "tri_state"))
      (node (ref "IC11") (pin "10") (pinfunction "+IN_10") (pintype "input"))
    )
    (net (code "61") (name "Net-(IC10A-QD)") (class "Default")
      (node (ref "IC10") (pin "3") (pinfunction "QD_3") (pintype "tri_state"))
      (node (ref "IC11") (pin "12") (pinfunction "+IN_12") (pintype "input"))
    )
    (net (code "62") (name "Net-(IC10A-QE)") (class "Default")
      (node (ref "IC10") (pin "4") (pinfunction "QE_4") (pintype "tri_state"))
      (node (ref "IC12") (pin "3") (pinfunction "+IN_3") (pintype "input"))
    )
    (net (code "63") (name "Net-(IC10A-QF)") (class "Default")
      (node (ref "IC10") (pin "5") (pinfunction "QF_5") (pintype "tri_state"))
      (node (ref "IC12") (pin "5") (pinfunction "+IN_5") (pintype "input"))
    )
    (net (code "64") (name "Net-(IC10A-QG)") (class "Default")
      (node (ref "IC10") (pin "6") (pinfunction "QG_6") (pintype "tri_state"))
      (node (ref "IC12") (pin "10") (pinfunction "+IN_10") (pintype "input"))
    )
    (net (code "65") (name "Net-(IC10A-QH)") (class "Default")
      (node (ref "IC10") (pin "7") (pinfunction "QH_7") (pintype "tri_state"))
      (node (ref "IC12") (pin "12") (pinfunction "+IN_12") (pintype "input"))
    )
    (net (code "66") (name "Net-(IC10A-RCK)") (class "Default")
      (node (ref "IC1") (pin "12") (pinfunction "RCK_12") (pintype "input"))
      (node (ref "IC10") (pin "12") (pinfunction "RCK_12") (pintype "input"))
      (node (ref "IC4") (pin "12") (pinfunction "RCK_12") (pintype "input"))
      (node (ref "IC7") (pin "12") (pinfunction "RCK_12") (pintype "input"))
      (node (ref "LATCH") (pin "1") (pinfunction "3_1") (pintype "passive"))
    )
    (net (code "67") (name "Net-(IC10A-SER)") (class "Default")
      (node (ref "IC10") (pin "14") (pinfunction "SER_14") (pintype "input"))
      (node (ref "IC7") (pin "9") (pinfunction "QH*_9") (pintype "tri_state"))
    )
    (net (code "68") (name "Net-(IC11A--IN)") (class "Default")
      (node (ref "IC11") (pin "1") (pinfunction "OUT_1") (pintype "output"))
      (node (ref "IC11") (pin "2") (pinfunction "-IN_2") (pintype "input"))
      (node (ref "R25") (pin "1") (pinfunction "1_1") (pintype "passive"))
    )
    (net (code "69") (name "Net-(IC11B--IN)") (class "Default")
      (node (ref "IC11") (pin "6") (pinfunction "-IN_6") (pintype "input"))
      (node (ref "IC11") (pin "7") (pinfunction "OUT_7") (pintype "output"))
      (node (ref "R26") (pin "1") (pinfunction "1_1") (pintype "passive"))
    )
    (net (code "70") (name "Net-(IC11C--IN)") (class "Default")
      (node (ref "IC11") (pin "8") (pinfunction "OUT_8") (pintype "output"))
      (node (ref "IC11") (pin "9") (pinfunction "-IN_9") (pintype "input"))
      (node (ref "R27") (pin "1") (pinfunction "1_1") (pintype "passive"))
    )
    (net (code "71") (name "Net-(IC11D--IN)") (class "Default")
      (node (ref "IC11") (pin "13") (pinfunction "-IN_13") (pintype "input"))
      (node (ref "IC11") (pin "14") (pinfunction "OUT_14") (pintype "output"))
      (node (ref "R28") (pin "1") (pinfunction "1_1") (pintype "passive"))
    )
    (net (code "72") (name "Net-(IC12A--IN)") (class "Default")
      (node (ref "IC12") (pin "1") (pinfunction "OUT_1") (pintype "output"))
      (node (ref "IC12") (pin "2") (pinfunction "-IN_2") (pintype "input"))
      (node (ref "R29") (pin "1") (pinfunction "1_1") (pintype "passive"))
    )
    (net (code "73") (name "Net-(IC12B--IN)") (class "Default")
      (node (ref "IC12") (pin "6") (pinfunction "-IN_6") (pintype "input"))
      (node (ref "IC12") (pin "7") (pinfunction "OUT_7") (pintype "output"))
      (node (ref "R30") (pin "1") (pinfunction "1_1") (pintype "passive"))
    )
    (net (code "74") (name "Net-(IC12C--IN)") (class "Default")
      (node (ref "IC12") (pin "8") (pinfunction "OUT_8") (pintype "output"))
      (node (ref "IC12") (pin "9") (pinfunction "-IN_9") (pintype "input"))
      (node (ref "R31") (pin "1") (pinfunction "1_1") (pintype "passive"))
    )
    (net (code "75") (name "Net-(IC12D--IN)") (class "Default")
      (node (ref "IC12") (pin "13") (pinfunction "-IN_13") (pintype "input"))
      (node (ref "IC12") (pin "14") (pinfunction "OUT_14") (pintype "output"))
      (node (ref "R32") (pin "1") (pinfunction "1_1") (pintype "passive"))
    )
    (net (code "76") (name "Net-(OUT1-3)") (class "Default")
      (node (ref "OUT1") (pin "1") (pinfunction "3_1") (pintype "passive"))
      (node (ref "R1") (pin "2") (pinfunction "2_2") (pintype "passive"))
    )
    (net (code "77") (name "Net-(OUT2-3)") (class "Default")
      (node (ref "OUT2") (pin "1") (pinfunction "3_1") (pintype "passive"))
      (node (ref "R2") (pin "2") (pinfunction "2_2") (pintype "passive"))
    )
    (net (code "78") (name "Net-(OUT3-3)") (class "Default")
      (node (ref "OUT3") (pin "1") (pinfunction "3_1") (pintype "passive"))
      (node (ref "R3") (pin "2") (pinfunction "2_2") (pintype "passive"))
    )
    (net (code "79") (name "Net-(OUT4-3)") (class "Default")
      (node (ref "OUT4") (pin "1") (pinfunction "3_1") (pintype "passive"))
      (node (ref "R4") (pin "2") (pinfunction "2_2") (pintype "passive"))
    )
    (net (code "80") (name "Net-(OUT5-3)") (class "Default")
      (node (ref "OUT5") (pin "1") (pinfunction "3_1") (pintype "passive"))
      (node (ref "R5") (pin "2") (pinfunction "2_2") (pintype "passive"))
    )
    (net (code "81") (name "Net-(OUT6-3)") (class "Default")
      (node (ref "OUT6") (pin "1") (pinfunction "3_1") (pintype "passive"))
      (node (ref "R6") (pin "2") (pinfunction "2_2") (pintype "passive"))
    )
    (net (code "82") (name "Net-(OUT7-3)") (class "Default")
      (node (ref "OUT7") (pin "1") (pinfunction "3_1") (pintype "passive"))
      (node (ref "R7") (pin "2") (pinfunction "2_2") (pintype "passive"))
    )
    (net (code "83") (name "Net-(OUT8-3)") (class "Default")
      (node (ref "OUT8") (pin "1") (pinfunction "3_1") (pintype "passive"))
      (node (ref "R8") (pin "2") (pinfunction "2_2") (pintype "passive"))
    )
    (net (code "84") (name "Net-(OUT9-3)") (class "Default")
      (node (ref "OUT9") (pin "1") (pinfunction "3_1") (pintype "passive"))
      (node (ref "R9") (pin "2") (pinfunction "2_2") (pintype "passive"))
    )
    (net (code "85") (name "Net-(OUT10-3)") (class "Default")
      (node (ref "OUT10") (pin "1") (pinfunction "3_1") (pintype "passive"))
      (node (ref "R10") (pin "2") (pinfunction "2_2") (pintype "passive"))
    )
    (net (code "86") (name "Net-(OUT11-3)") (class "Default")
      (node (ref "OUT11") (pin "1") (pinfunction "3_1") (pintype "passive"))
      (node (ref "R11") (pin "2") (pinfunction "2_2") (pintype "passive"))
    )
    (net (code "87") (name "Net-(OUT12-3)") (class "Default")
      (node (ref "OUT12") (pin "1") (pinfunction "3_1") (pintype "passive"))
      (node (ref "R12") (pin "2") (pinfunction "2_2") (pintype "passive"))
    )
    (net (code "88") (name "Net-(OUT13-3)") (class "Default")
      (node (ref "OUT13") (pin "1") (pinfunction "3_1") (pintype "passive"))
      (node (ref "R13") (pin "2") (pinfunction "2_2") (pintype "passive"))
    )
    (net (code "89") (name "Net-(OUT14-3)") (class "Default")
      (node (ref "OUT14") (pin "1") (pinfunction "3_1") (pintype "passive"))
      (node (ref "R14") (pin "2") (pinfunction "2_2") (pintype "passive"))
    )
    (net (code "90") (name "Net-(OUT15-3)") (class "Default")
      (node (ref "OUT15") (pin "1") (pinfunction "3_1") (pintype "passive"))
      (node (ref "R15") (pin "2") (pinfunction "2_2") (pintype "passive"))
    )
    (net (code "91") (name "Net-(OUT16-3)") (class "Default")
      (node (ref "OUT16") (pin "1") (pinfunction "3_1") (pintype "passive"))
      (node (ref "R16") (pin "2") (pinfunction "2_2") (pintype "passive"))
    )
    (net (code "92") (name "Net-(OUT17-3)") (class "Default")
      (node (ref "OUT17") (pin "1") (pinfunction "3_1") (pintype "passive"))
      (node (ref "R17") (pin "2") (pinfunction "2_2") (pintype "passive"))
    )
    (net (code "93") (name "Net-(OUT18-3)") (class "Default")
      (node (ref "OUT18") (pin "1") (pinfunction "3_1") (pintype "passive"))
      (node (ref "R18") (pin "2") (pinfunction "2_2") (pintype "passive"))
    )
    (net (code "94") (name "Net-(OUT19-3)") (class "Default")
      (node (ref "OUT19") (pin "1") (pinfunction "3_1") (pintype "passive"))
      (node (ref "R19") (pin "2") (pinfunction "2_2") (pintype "passive"))
    )
    (net (code "95") (name "Net-(OUT20-3)") (class "Default")
      (node (ref "OUT20") (pin "1") (pinfunction "3_1") (pintype "passive"))
      (node (ref "R20") (pin "2") (pinfunction "2_2") (pintype "passive"))
    )
    (net (code "96") (name "Net-(OUT21-3)") (class "Default")
      (node (ref "OUT21") (pin "1") (pinfunction "3_1") (pintype "passive"))
      (node (ref "R21") (pin "2") (pinfunction "2_2") (pintype "passive"))
    )
    (net (code "97") (name "Net-(OUT22-3)") (class "Default")
      (node (ref "OUT22") (pin "1") (pinfunction "3_1") (pintype "passive"))
      (node (ref "R22") (pin "2") (pinfunction "2_2") (pintype "passive"))
    )
    (net (code "98") (name "Net-(OUT23-3)") (class "Default")
      (node (ref "OUT23") (pin "1") (pinfunction "3_1") (pintype "passive"))
      (node (ref "R23") (pin "2") (pinfunction "2_2") (pintype "passive"))
    )
    (net (code "99") (name "Net-(OUT24-3)") (class "Default")
      (node (ref "OUT24") (pin "1") (pinfunction "3_1") (pintype "passive"))
      (node (ref "R24") (pin "2") (pinfunction "2_2") (pintype "passive"))
    )
    (net (code "100") (name "Net-(OUT25-3)") (class "Default")
      (node (ref "OUT25") (pin "1") (pinfunction "3_1") (pintype "passive"))
      (node (ref "R25") (pin "2") (pinfunction "2_2") (pintype "passive"))
    )
    (net (code "101") (name "Net-(OUT26-3)") (class "Default")
      (node (ref "OUT26") (pin "1") (pinfunction "3_1") (pintype "passive"))
      (node (ref "R26") (pin "2") (pinfunction "2_2") (pintype "passive"))
    )
    (net (code "102") (name "Net-(OUT27-3)") (class "Default")
      (node (ref "OUT27") (pin "1") (pinfunction "3_1") (pintype "passive"))
      (node (ref "R27") (pin "2") (pinfunction "2_2") (pintype "passive"))
    )
    (net (code "103") (name "Net-(OUT28-3)") (class "Default")
      (node (ref "OUT28") (pin "1") (pinfunction "3_1") (pintype "passive"))
      (node (ref "R28") (pin "2") (pinfunction "2_2") (pintype "passive"))
    )
    (net (code "104") (name "Net-(OUT29-3)") (class "Default")
      (node (ref "OUT29") (pin "1") (pinfunction "3_1") (pintype "passive"))
      (node (ref "R29") (pin "2") (pinfunction "2_2") (pintype "passive"))
    )
    (net (code "105") (name "Net-(OUT30-3)") (class "Default")
      (node (ref "OUT30") (pin "1") (pinfunction "3_1") (pintype "passive"))
      (node (ref "R30") (pin "2") (pinfunction "2_2") (pintype "passive"))
    )
    (net (code "106") (name "Net-(OUT31-3)") (class "Default")
      (node (ref "OUT31") (pin "1") (pinfunction "3_1") (pintype "passive"))
      (node (ref "R31") (pin "2") (pinfunction "2_2") (pintype "passive"))
    )
    (net (code "107") (name "Net-(OUT32-3)") (class "Default")
      (node (ref "OUT32") (pin "1") (pinfunction "3_1") (pintype "passive"))
      (node (ref "R32") (pin "2") (pinfunction "2_2") (pintype "passive"))
    )
  )
)
